# big-auv-power.net
KiCad netlist of a schematic drawn in Altium Designer
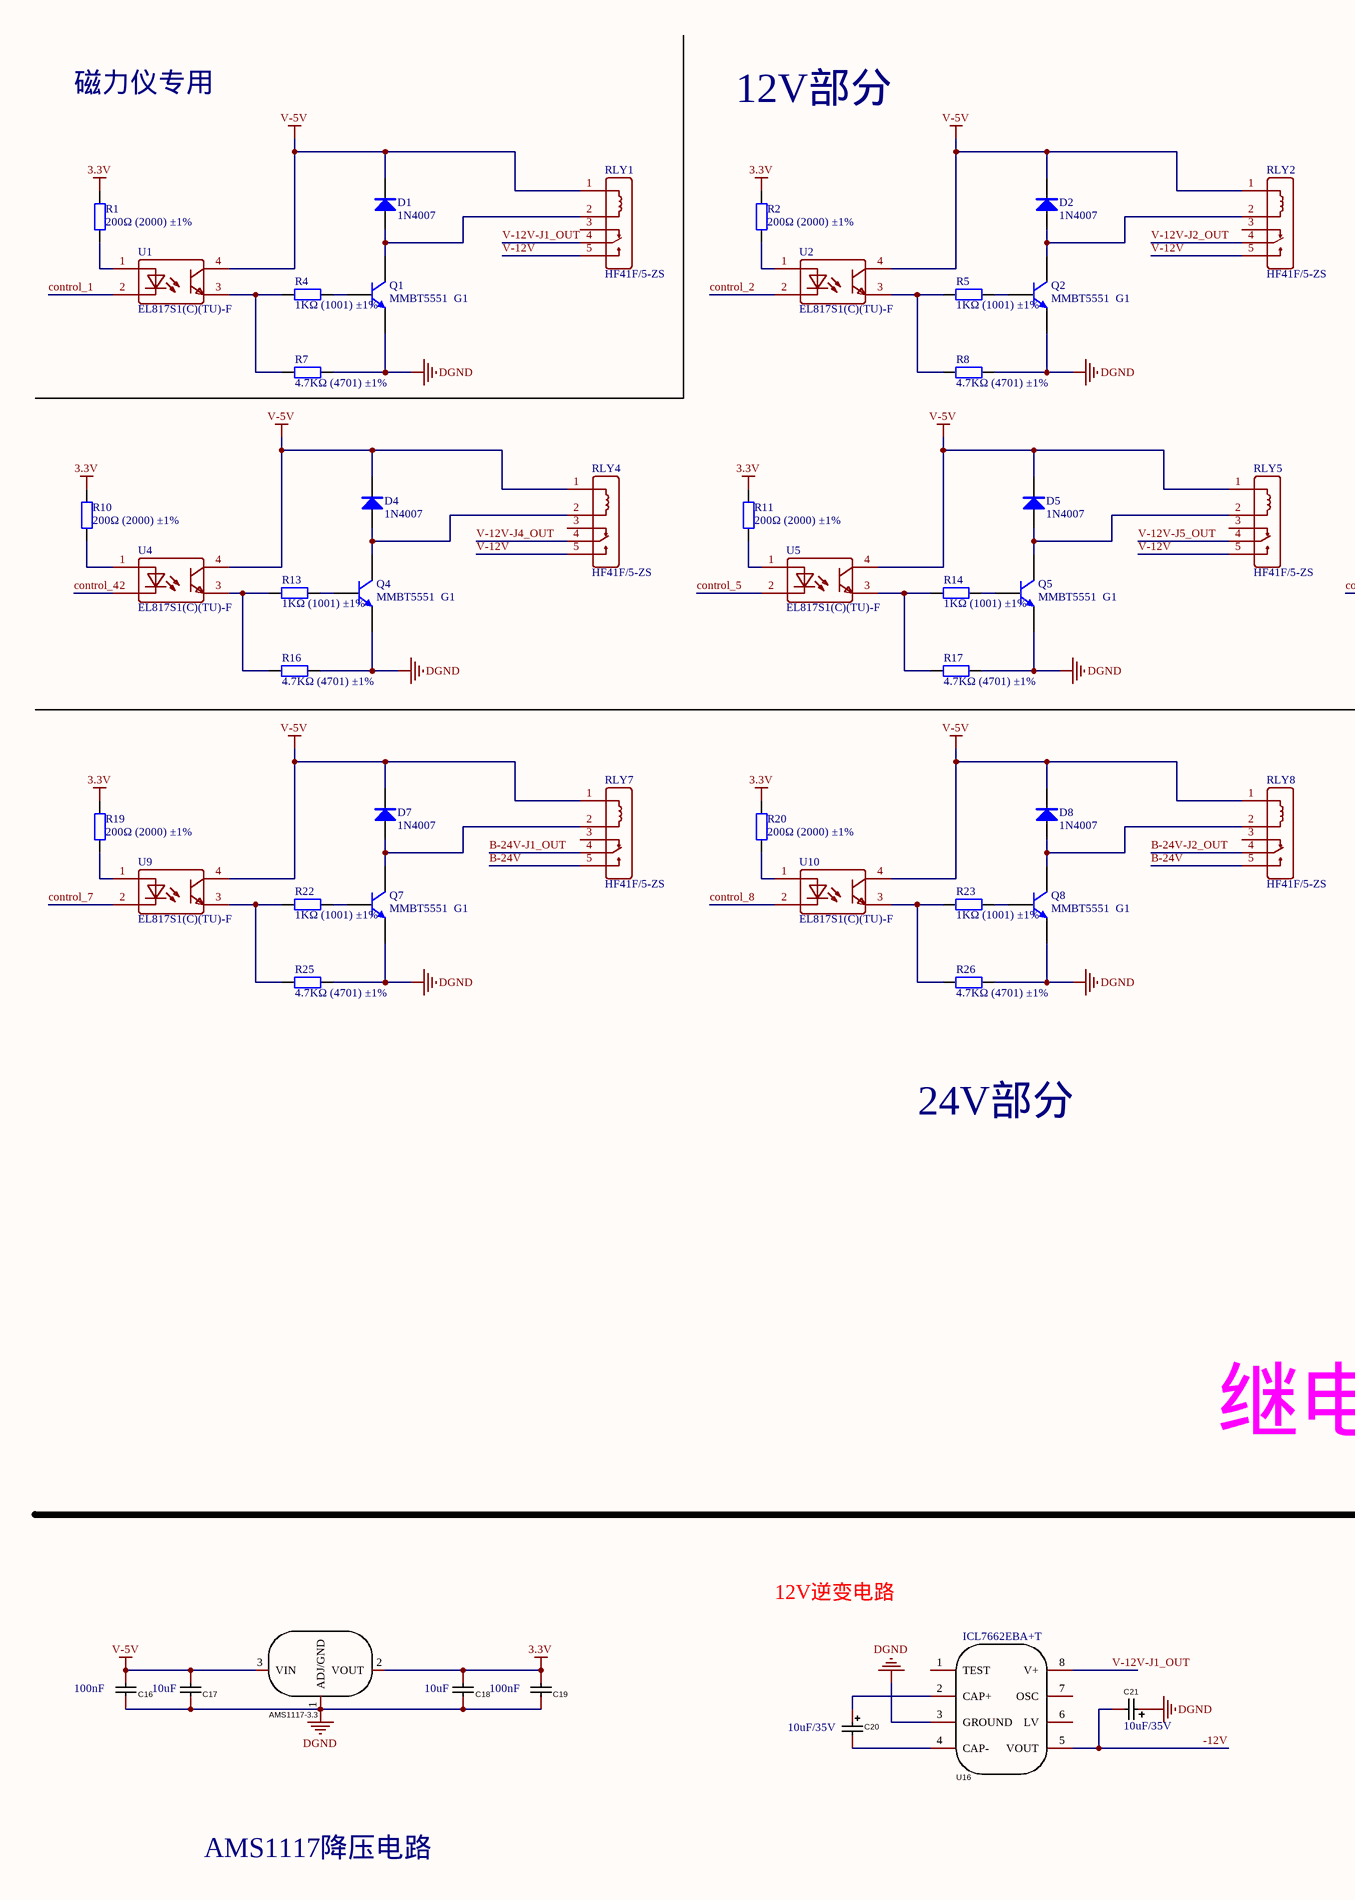
[diagram p0: big-auv-power.SchDoc, left]
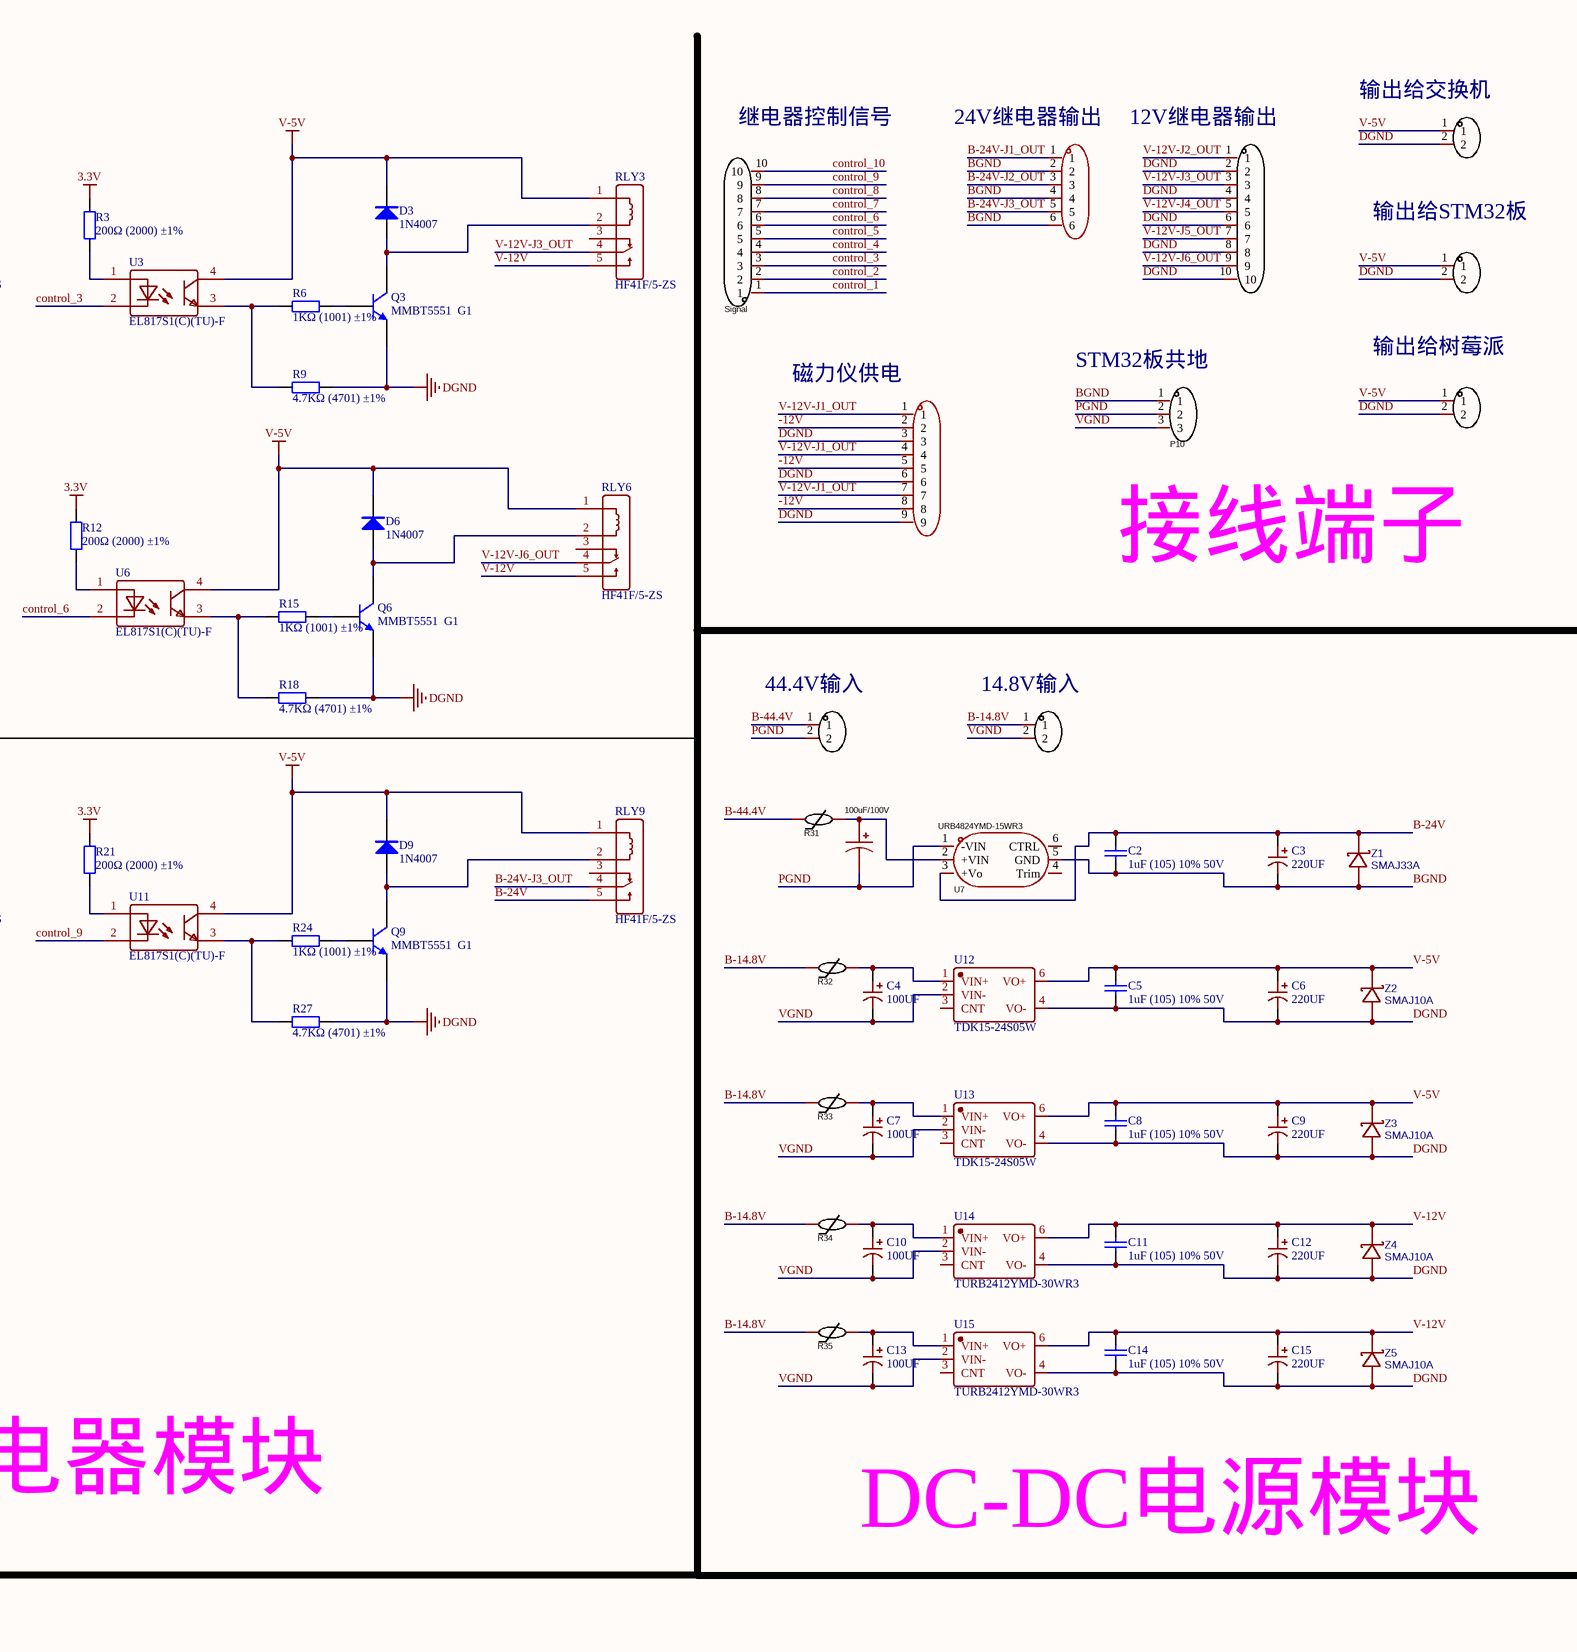
[diagram p1: big-auv-power.SchDoc, right]

(export (version "E")
  (design (tool "Eeschema 10.0.6"))
  (components
    (comp (ref "12V")
      (value "KF2EDGR-3.5-10P")
      (footprint "CONN-TH_10P-P3.50_KF2EDGR-3.5-10P")
      (fields (field (name "MANUFACTURER") "KEFA(科发)"))
      (libsource (lib "LC_Components") (part "KF2EDGR-3.5-10P"))
    )
    (comp (ref "24V")
      (value "KF2EDGR-3.5-6P")
      (footprint "CONN-TH_6P-P3.50_KF2EDGR-3.5-6P")
      (fields (field (name "MANUFACTURER") "KEFA(科发)"))
      (libsource (lib "LC_Components") (part "KF2EDGR-3.5-6P"))
    )
    (comp (ref "AMS1117-3.3")
      (value "A1117-3.3")
      (footprint "SOT-223-3_L6.5-W3.4-P2.30-LS7.0-BR-1")
      (fields (field (name "MANUFACTURER") "IDCHIP(英锐芯)"))
      (libsource (lib "LC_Components") (part "AMS1117-3.3"))
    )
    (comp (ref "C1")
      (value "100uF/100V")
      (footprint "CAP-SMD_BD12.5-L13.0-W13.0-FD-LS13.8")
      (description "100uF 100V电解电容")
      (fields (field (name "MANUFACTURER") "ROQANG(容强)") (field (name "MANUFACTURER PART") "RVT2A101M1213"))
      (libsource (lib "LC_Components") (part "RVT2A101M1213"))
    )
    (comp (ref "C2")
      (value "1uF (105) 10% 50V")
      (footprint "C0603")
      (description "贴片电容")
      (libsource (lib "2-Cap") (part "0603 1uF (105) 10% 50V"))
    )
    (comp (ref "C3") (value "220UF") (footprint "SMD-C") (libsource (lib "big-auv-power") (part "220UF")))
    (comp (ref "C4") (value "100UF") (footprint "SMD-C") (libsource (lib "big-auv-power") (part "100UF")))
    (comp (ref "C5")
      (value "1uF (105) 10% 50V")
      (footprint "C0603")
      (description "贴片电容")
      (libsource (lib "2-Cap") (part "0603 1uF (105) 10% 50V"))
    )
    (comp (ref "C6") (value "220UF") (footprint "SMD-C") (libsource (lib "big-auv-power") (part "220UF")))
    (comp (ref "C7") (value "100UF") (footprint "SMD-C") (libsource (lib "big-auv-power") (part "100UF")))
    (comp (ref "C8")
      (value "1uF (105) 10% 50V")
      (footprint "C0603")
      (description "贴片电容")
      (libsource (lib "2-Cap") (part "0603 1uF (105) 10% 50V"))
    )
    (comp (ref "C9") (value "220UF") (footprint "SMD-C") (libsource (lib "big-auv-power") (part "220UF")))
    (comp (ref "C10") (value "100UF") (footprint "SMD-C") (libsource (lib "big-auv-power") (part "100UF")))
    (comp (ref "C11")
      (value "1uF (105) 10% 50V")
      (footprint "C0603")
      (description "贴片电容")
      (libsource (lib "2-Cap") (part "0603 1uF (105) 10% 50V"))
    )
    (comp (ref "C12") (value "220UF") (footprint "SMD-C") (libsource (lib "big-auv-power") (part "220UF")))
    (comp (ref "C13") (value "100UF") (footprint "SMD-C") (libsource (lib "big-auv-power") (part "100UF")))
    (comp (ref "C14")
      (value "1uF (105) 10% 50V")
      (footprint "C0603")
      (description "贴片电容")
      (libsource (lib "2-Cap") (part "0603 1uF (105) 10% 50V"))
    )
    (comp (ref "C15") (value "220UF") (footprint "SMD-C") (libsource (lib "big-auv-power") (part "220UF")))
    (comp (ref "C16")
      (value "100nF")
      (footprint "C0603")
      (description "0603电容")
      (fields (field (name "MANUFACTURER") "FH(风华)") (field (name "MANUFACTURER PART") "0603B104K500NT"))
      (libsource (lib "LC_Components") (part "0603B104K500NT"))
    )
    (comp (ref "C17")
      (value "10uF")
      (footprint "C0603")
      (description "0603电容")
      (fields (field (name "MANUFACTURER") "FH(风华)") (field (name "MANUFACTURER PART") "0603B104K500NT"))
      (libsource (lib "LC_Components") (part "0603B104K500NT"))
    )
    (comp (ref "C18")
      (value "10uF")
      (footprint "C0603")
      (description "0603电容")
      (fields (field (name "MANUFACTURER") "FH(风华)") (field (name "MANUFACTURER PART") "0603B104K500NT"))
      (libsource (lib "LC_Components") (part "0603B104K500NT"))
    )
    (comp (ref "C19")
      (value "100nF")
      (footprint "C0603")
      (description "0603电容")
      (fields (field (name "MANUFACTURER") "FH(风华)") (field (name "MANUFACTURER PART") "0603B104K500NT"))
      (libsource (lib "LC_Components") (part "0603B104K500NT"))
    )
    (comp (ref "C20")
      (value "10uF/35V")
      (footprint "CASE-C_6032")
      (description "10uF/35V钽电容")
      (fields (field (name "MANUFACTURER") "Kyocera AVX") (field (name "MANUFACTURER PART") "TAJC106K035RNJ"))
      (libsource (lib "LC_Components") (part "TAJC106K035RNJ"))
    )
    (comp (ref "C21")
      (value "10uF/35V")
      (footprint "CASE-C_6032")
      (description "10uF/35V钽电容")
      (fields (field (name "MANUFACTURER") "Kyocera AVX") (field (name "MANUFACTURER PART") "TAJC106K035RNJ"))
      (libsource (lib "LC_Components") (part "TAJC106K035RNJ"))
    )
    (comp (ref "CILIYI")
      (value "KF2EDGR-3.5-9P")
      (footprint "CONN-TH_9P-P3.50_KF2EDGR-3.5-9P")
      (fields (field (name "MANUFACTURER") "KEFA(科发)"))
      (libsource (lib "LC_Components") (part "KF2EDGR-3.5-9P"))
    )
    (comp (ref "D1")
      (value "1N4007")
      (footprint "SMA(DO-214AC)_S2")
      (description "整流二极管")
      (fields (field (name "版权归属") "源创客"))
      (libsource (lib "4-Diode") (part "1N4007"))
    )
    (comp (ref "D2")
      (value "1N4007")
      (footprint "SMA(DO-214AC)_S2")
      (description "整流二极管")
      (fields (field (name "版权归属") "源创客"))
      (libsource (lib "4-Diode") (part "1N4007"))
    )
    (comp (ref "D3")
      (value "1N4007")
      (footprint "SMA(DO-214AC)_S2")
      (description "整流二极管")
      (fields (field (name "版权归属") "源创客"))
      (libsource (lib "4-Diode") (part "1N4007"))
    )
    (comp (ref "D4")
      (value "1N4007")
      (footprint "SMA(DO-214AC)_S2")
      (description "整流二极管")
      (fields (field (name "版权归属") "源创客"))
      (libsource (lib "4-Diode") (part "1N4007"))
    )
    (comp (ref "D5")
      (value "1N4007")
      (footprint "SMA(DO-214AC)_S2")
      (description "整流二极管")
      (fields (field (name "版权归属") "源创客"))
      (libsource (lib "4-Diode") (part "1N4007"))
    )
    (comp (ref "D6")
      (value "1N4007")
      (footprint "SMA(DO-214AC)_S2")
      (description "整流二极管")
      (fields (field (name "版权归属") "源创客"))
      (libsource (lib "4-Diode") (part "1N4007"))
    )
    (comp (ref "D7")
      (value "1N4007")
      (footprint "SMA(DO-214AC)_S2")
      (description "整流二极管")
      (fields (field (name "版权归属") "源创客"))
      (libsource (lib "4-Diode") (part "1N4007"))
    )
    (comp (ref "D8")
      (value "1N4007")
      (footprint "SMA(DO-214AC)_S2")
      (description "整流二极管")
      (fields (field (name "版权归属") "源创客"))
      (libsource (lib "4-Diode") (part "1N4007"))
    )
    (comp (ref "D9")
      (value "1N4007")
      (footprint "SMA(DO-214AC)_S2")
      (description "整流二极管")
      (fields (field (name "版权归属") "源创客"))
      (libsource (lib "4-Diode") (part "1N4007"))
    )
    (comp (ref "JP1")
      (value "KF2EDGR-3.81-2P")
      (footprint "CONN-TH_2P-P3.81_KF2EDGR-3.81-2P")
      (fields (field (name "MANUFACTURER") "KEFA(科发)"))
      (libsource (lib "LC_Components") (part "KF2EDGR-3.81-2P"))
    )
    (comp (ref "JP2")
      (value "KF2EDGR-3.81-2P")
      (footprint "CONN-TH_2P-P3.81_KF2EDGR-3.81-2P")
      (fields (field (name "MANUFACTURER") "KEFA(科发)"))
      (libsource (lib "LC_Components") (part "KF2EDGR-3.81-2P"))
    )
    (comp (ref "JP3")
      (value "KF2EDGR-3.81-2P")
      (footprint "CONN-TH_2P-P3.81_KF2EDGR-3.81-2P")
      (fields (field (name "MANUFACTURER") "KEFA(科发)"))
      (libsource (lib "LC_Components") (part "KF2EDGR-3.81-2P"))
    )
    (comp (ref "P6")
      (value "KF2EDGV-5.08-2P")
      (footprint "CONN-TH_P5.08_KF2EDGV-5.08-2P")
      (fields (field (name "MANUFACTURER") "KEFA(科发)"))
      (libsource (lib "LC_Components") (part "KF2EDGV-5.08-2P"))
    )
    (comp (ref "P7")
      (value "KF2EDGV-5.08-2P")
      (footprint "CONN-TH_P5.08_KF2EDGV-5.08-2P")
      (fields (field (name "MANUFACTURER") "KEFA(科发)"))
      (libsource (lib "LC_Components") (part "KF2EDGV-5.08-2P"))
    )
    (comp (ref "P10")
      (value "KF2EDGR-3.81-3P")
      (footprint "CONN-TH_3P-P3.81_KF2EDGR-3.81-3P")
      (fields (field (name "MANUFACTURER") "KEFA(科发)"))
      (libsource (lib "LC_Components") (part "KF2EDGR-3.81-3P"))
    )
    (comp (ref "Q1")
      (value "MMBT5551  G1")
      (footprint "SOT-23-3_L2.9-W1.3-P1.90-LS2.4-BR")
      (description "三极管")
      (libsource (lib "7-Transistor_NPN") (part "SOT-23 MMBT5551  G1"))
    )
    (comp (ref "Q2")
      (value "MMBT5551  G1")
      (footprint "SOT-23-3_L2.9-W1.3-P1.90-LS2.4-BR")
      (description "三极管")
      (libsource (lib "7-Transistor_NPN") (part "SOT-23 MMBT5551  G1"))
    )
    (comp (ref "Q3")
      (value "MMBT5551  G1")
      (footprint "SOT-23-3_L2.9-W1.3-P1.90-LS2.4-BR")
      (description "三极管")
      (libsource (lib "7-Transistor_NPN") (part "SOT-23 MMBT5551  G1"))
    )
    (comp (ref "Q4")
      (value "MMBT5551  G1")
      (footprint "SOT-23-3_L2.9-W1.3-P1.90-LS2.4-BR")
      (description "三极管")
      (libsource (lib "7-Transistor_NPN") (part "SOT-23 MMBT5551  G1"))
    )
    (comp (ref "Q5")
      (value "MMBT5551  G1")
      (footprint "SOT-23-3_L2.9-W1.3-P1.90-LS2.4-BR")
      (description "三极管")
      (libsource (lib "7-Transistor_NPN") (part "SOT-23 MMBT5551  G1"))
    )
    (comp (ref "Q6")
      (value "MMBT5551  G1")
      (footprint "SOT-23-3_L2.9-W1.3-P1.90-LS2.4-BR")
      (description "三极管")
      (libsource (lib "7-Transistor_NPN") (part "SOT-23 MMBT5551  G1"))
    )
    (comp (ref "Q7")
      (value "MMBT5551  G1")
      (footprint "SOT-23-3_L2.9-W1.3-P1.90-LS2.4-BR")
      (description "三极管")
      (libsource (lib "7-Transistor_NPN") (part "SOT-23 MMBT5551  G1"))
    )
    (comp (ref "Q8")
      (value "MMBT5551  G1")
      (footprint "SOT-23-3_L2.9-W1.3-P1.90-LS2.4-BR")
      (description "三极管")
      (libsource (lib "7-Transistor_NPN") (part "SOT-23 MMBT5551  G1"))
    )
    (comp (ref "Q9")
      (value "MMBT5551  G1")
      (footprint "SOT-23-3_L2.9-W1.3-P1.90-LS2.4-BR")
      (description "三极管")
      (libsource (lib "7-Transistor_NPN") (part "SOT-23 MMBT5551  G1"))
    )
    (comp (ref "R1")
      (value "200Ω (2000) ±1%")
      (footprint "R0603")
      (description "贴片电阻")
      (libsource (lib "1-RES") (part "0603 200Ω (2000) 1%"))
    )
    (comp (ref "R2")
      (value "200Ω (2000) ±1%")
      (footprint "R0603")
      (description "贴片电阻")
      (libsource (lib "1-RES") (part "0603 200Ω (2000) 1%"))
    )
    (comp (ref "R3")
      (value "200Ω (2000) ±1%")
      (footprint "R0603")
      (description "贴片电阻")
      (libsource (lib "1-RES") (part "0603 200Ω (2000) 1%"))
    )
    (comp (ref "R4")
      (value "1KΩ (1001) ±1%")
      (footprint "R0603")
      (description "贴片电阻")
      (libsource (lib "1-RES") (part "0603 1KΩ (1001) 1%"))
    )
    (comp (ref "R5")
      (value "1KΩ (1001) ±1%")
      (footprint "R0603")
      (description "贴片电阻")
      (libsource (lib "1-RES") (part "0603 1KΩ (1001) 1%"))
    )
    (comp (ref "R6")
      (value "1KΩ (1001) ±1%")
      (footprint "R0603")
      (description "贴片电阻")
      (libsource (lib "1-RES") (part "0603 1KΩ (1001) 1%"))
    )
    (comp (ref "R7")
      (value "4.7KΩ (4701) ±1%")
      (footprint "R0603")
      (description "贴片电阻")
      (libsource (lib "1-RES") (part "0603 4.7KΩ (4701) 1%"))
    )
    (comp (ref "R8")
      (value "4.7KΩ (4701) ±1%")
      (footprint "R0603")
      (description "贴片电阻")
      (libsource (lib "1-RES") (part "0603 4.7KΩ (4701) 1%"))
    )
    (comp (ref "R9")
      (value "4.7KΩ (4701) ±1%")
      (footprint "R0603")
      (description "贴片电阻")
      (libsource (lib "1-RES") (part "0603 4.7KΩ (4701) 1%"))
    )
    (comp (ref "R10")
      (value "200Ω (2000) ±1%")
      (footprint "R0603")
      (description "贴片电阻")
      (libsource (lib "1-RES") (part "0603 200Ω (2000) 1%"))
    )
    (comp (ref "R11")
      (value "200Ω (2000) ±1%")
      (footprint "R0603")
      (description "贴片电阻")
      (libsource (lib "1-RES") (part "0603 200Ω (2000) 1%"))
    )
    (comp (ref "R12")
      (value "200Ω (2000) ±1%")
      (footprint "R0603")
      (description "贴片电阻")
      (libsource (lib "1-RES") (part "0603 200Ω (2000) 1%"))
    )
    (comp (ref "R13")
      (value "1KΩ (1001) ±1%")
      (footprint "R0603")
      (description "贴片电阻")
      (libsource (lib "1-RES") (part "0603 1KΩ (1001) 1%"))
    )
    (comp (ref "R14")
      (value "1KΩ (1001) ±1%")
      (footprint "R0603")
      (description "贴片电阻")
      (libsource (lib "1-RES") (part "0603 1KΩ (1001) 1%"))
    )
    (comp (ref "R15")
      (value "1KΩ (1001) ±1%")
      (footprint "R0603")
      (description "贴片电阻")
      (libsource (lib "1-RES") (part "0603 1KΩ (1001) 1%"))
    )
    (comp (ref "R16")
      (value "4.7KΩ (4701) ±1%")
      (footprint "R0603")
      (description "贴片电阻")
      (libsource (lib "1-RES") (part "0603 4.7KΩ (4701) 1%"))
    )
    (comp (ref "R17")
      (value "4.7KΩ (4701) ±1%")
      (footprint "R0603")
      (description "贴片电阻")
      (libsource (lib "1-RES") (part "0603 4.7KΩ (4701) 1%"))
    )
    (comp (ref "R18")
      (value "4.7KΩ (4701) ±1%")
      (footprint "R0603")
      (description "贴片电阻")
      (libsource (lib "1-RES") (part "0603 4.7KΩ (4701) 1%"))
    )
    (comp (ref "R19")
      (value "200Ω (2000) ±1%")
      (footprint "R0603")
      (description "贴片电阻")
      (libsource (lib "1-RES") (part "0603 200Ω (2000) 1%"))
    )
    (comp (ref "R20")
      (value "200Ω (2000) ±1%")
      (footprint "R0603")
      (description "贴片电阻")
      (libsource (lib "1-RES") (part "0603 200Ω (2000) 1%"))
    )
    (comp (ref "R21")
      (value "200Ω (2000) ±1%")
      (footprint "R0603")
      (description "贴片电阻")
      (libsource (lib "1-RES") (part "0603 200Ω (2000) 1%"))
    )
    (comp (ref "R22")
      (value "1KΩ (1001) ±1%")
      (footprint "R0603")
      (description "贴片电阻")
      (libsource (lib "1-RES") (part "0603 1KΩ (1001) 1%"))
    )
    (comp (ref "R23")
      (value "1KΩ (1001) ±1%")
      (footprint "R0603")
      (description "贴片电阻")
      (libsource (lib "1-RES") (part "0603 1KΩ (1001) 1%"))
    )
    (comp (ref "R24")
      (value "1KΩ (1001) ±1%")
      (footprint "R0603")
      (description "贴片电阻")
      (libsource (lib "1-RES") (part "0603 1KΩ (1001) 1%"))
    )
    (comp (ref "R25")
      (value "4.7KΩ (4701) ±1%")
      (footprint "R0603")
      (description "贴片电阻")
      (libsource (lib "1-RES") (part "0603 4.7KΩ (4701) 1%"))
    )
    (comp (ref "R26")
      (value "4.7KΩ (4701) ±1%")
      (footprint "R0603")
      (description "贴片电阻")
      (libsource (lib "1-RES") (part "0603 4.7KΩ (4701) 1%"))
    )
    (comp (ref "R27")
      (value "4.7KΩ (4701) ±1%")
      (footprint "R0603")
      (description "贴片电阻")
      (libsource (lib "1-RES") (part "0603 4.7KΩ (4701) 1%"))
    )
    (comp (ref "R31")
      (value "MF72 22D9")
      (footprint "RES-TH_L12.5-W5.1-P7.50-D1.2-S2.20")
      (description "NTC热敏电阻")
      (fields (field (name "MANUFACTURER") "时恒") (field (name "POWER") "2W"))
      (libsource (lib "LC_Components") (part "MF72 22D9"))
    )
    (comp (ref "R32")
      (value "MF72 22D9")
      (footprint "RES-TH_L12.5-W5.1-P7.50-D1.2-S2.20")
      (description "NTC热敏电阻")
      (fields (field (name "MANUFACTURER") "时恒") (field (name "POWER") "2W"))
      (libsource (lib "LC_Components") (part "MF72 22D9"))
    )
    (comp (ref "R33")
      (value "MF72 22D9")
      (footprint "RES-TH_L12.5-W5.1-P7.50-D1.2-S2.20")
      (description "NTC热敏电阻")
      (fields (field (name "MANUFACTURER") "时恒") (field (name "POWER") "2W"))
      (libsource (lib "LC_Components") (part "MF72 22D9"))
    )
    (comp (ref "R34")
      (value "MF72 22D9")
      (footprint "RES-TH_L12.5-W5.1-P7.50-D1.2-S2.20")
      (description "NTC热敏电阻")
      (fields (field (name "MANUFACTURER") "时恒") (field (name "POWER") "2W"))
      (libsource (lib "LC_Components") (part "MF72 22D9"))
    )
    (comp (ref "R35")
      (value "MF72 22D9")
      (footprint "RES-TH_L12.5-W5.1-P7.50-D1.2-S2.20")
      (description "NTC热敏电阻")
      (fields (field (name "MANUFACTURER") "时恒") (field (name "POWER") "2W"))
      (libsource (lib "LC_Components") (part "MF72 22D9"))
    )
    (comp (ref "RLY1")
      (value "HF41F/5-ZS")
      (footprint "HF41F/5-ZS")
      (libsource (lib "big-auv-power") (part "HF41F/5-ZS"))
    )
    (comp (ref "RLY2")
      (value "HF41F/5-ZS")
      (footprint "HF41F/5-ZS")
      (libsource (lib "big-auv-power") (part "HF41F/5-ZS"))
    )
    (comp (ref "RLY3")
      (value "HF41F/5-ZS")
      (footprint "HF41F/5-ZS")
      (libsource (lib "big-auv-power") (part "HF41F/5-ZS"))
    )
    (comp (ref "RLY4")
      (value "HF41F/5-ZS")
      (footprint "HF41F/5-ZS")
      (libsource (lib "big-auv-power") (part "HF41F/5-ZS"))
    )
    (comp (ref "RLY5")
      (value "HF41F/5-ZS")
      (footprint "HF41F/5-ZS")
      (libsource (lib "big-auv-power") (part "HF41F/5-ZS"))
    )
    (comp (ref "RLY6")
      (value "HF41F/5-ZS")
      (footprint "HF41F/5-ZS")
      (libsource (lib "big-auv-power") (part "HF41F/5-ZS"))
    )
    (comp (ref "RLY7")
      (value "HF41F/5-ZS")
      (footprint "HF41F/5-ZS")
      (libsource (lib "big-auv-power") (part "HF41F/5-ZS"))
    )
    (comp (ref "RLY8")
      (value "HF41F/5-ZS")
      (footprint "HF41F/5-ZS")
      (libsource (lib "big-auv-power") (part "HF41F/5-ZS"))
    )
    (comp (ref "RLY9")
      (value "HF41F/5-ZS")
      (footprint "HF41F/5-ZS")
      (libsource (lib "big-auv-power") (part "HF41F/5-ZS"))
    )
    (comp (ref "Signal")
      (value "KF2EDGR-3.5-10P")
      (footprint "CONN-TH_10P-P3.50_KF2EDGR-3.5-10P")
      (fields (field (name "MANUFACTURER") "KEFA(科发)"))
      (libsource (lib "LC_Components") (part "KF2EDGR-3.5-10P"))
    )
    (comp (ref "U1")
      (value "EL817S1(C)(TU)-F")
      (footprint "EL817S1(C)(TU)-F")
      (libsource (lib "big-auv-power") (part "EL817S1(C)(TU)-F"))
    )
    (comp (ref "U2")
      (value "EL817S1(C)(TU)-F")
      (footprint "EL817S1(C)(TU)-F")
      (libsource (lib "big-auv-power") (part "EL817S1(C)(TU)-F"))
    )
    (comp (ref "U3")
      (value "EL817S1(C)(TU)-F")
      (footprint "EL817S1(C)(TU)-F")
      (libsource (lib "big-auv-power") (part "EL817S1(C)(TU)-F"))
    )
    (comp (ref "U4")
      (value "EL817S1(C)(TU)-F")
      (footprint "EL817S1(C)(TU)-F")
      (libsource (lib "big-auv-power") (part "EL817S1(C)(TU)-F"))
    )
    (comp (ref "U5")
      (value "EL817S1(C)(TU)-F")
      (footprint "EL817S1(C)(TU)-F")
      (libsource (lib "big-auv-power") (part "EL817S1(C)(TU)-F"))
    )
    (comp (ref "U6")
      (value "EL817S1(C)(TU)-F")
      (footprint "EL817S1(C)(TU)-F")
      (libsource (lib "big-auv-power") (part "EL817S1(C)(TU)-F"))
    )
    (comp (ref "U7")
      (value "URB4824YMD-15WR3")
      (footprint "PWRM-TH_YLPTEC_URBXXXXYMD-15WR3")
      (description "48V转24V降压模块")
      (fields (field (name "MANUFACTURER") "YLPTEC(易川)") (field (name "POWER") "15W"))
      (libsource (lib "LC_Components") (part "URB4824YMD-15WR3_C5369771"))
    )
    (comp (ref "U9")
      (value "EL817S1(C)(TU)-F")
      (footprint "EL817S1(C)(TU)-F")
      (libsource (lib "big-auv-power") (part "EL817S1(C)(TU)-F"))
    )
    (comp (ref "U10")
      (value "EL817S1(C)(TU)-F")
      (footprint "EL817S1(C)(TU)-F")
      (libsource (lib "big-auv-power") (part "EL817S1(C)(TU)-F"))
    )
    (comp (ref "U11")
      (value "EL817S1(C)(TU)-F")
      (footprint "EL817S1(C)(TU)-F")
      (libsource (lib "big-auv-power") (part "EL817S1(C)(TU)-F"))
    )
    (comp (ref "U12")
      (value "TDK15-24S05W")
      (footprint "TDK15-24S05")
      (libsource (lib "big-auv-power") (part "TDK15-24S05"))
    )
    (comp (ref "U13")
      (value "TDK15-24S05W")
      (footprint "TDK15-24S05")
      (libsource (lib "big-auv-power") (part "TDK15-24S05"))
    )
    (comp (ref "U14")
      (value "TURB2412YMD-30WR3")
      (footprint "TDK15-24S05")
      (libsource (lib "big-auv-power") (part "TDK15-24S05"))
    )
    (comp (ref "U15")
      (value "TURB2412YMD-30WR3")
      (footprint "TDK15-24S05")
      (libsource (lib "big-auv-power") (part "TDK15-24S05"))
    )
    (comp (ref "U16")
      (value "ICL7662EBA+T")
      (footprint "SOIC-8_L5.0-W4.0-P1.27-LS6.0-BL")
      (description "宽幅电压逆变")
      (fields (field (name "MANUFACTURER") "ADI(亚德诺)/MAXIM(美信)"))
      (libsource (lib "LC_Components") (part "ICL7662EBA+T"))
    )
    (comp (ref "Z1")
      (value "SMAJ33A")
      (footprint "SMA(DO-214AC)")
      (description "TVS二极管")
      (fields
        (field (name "BOM_SUPPLIER PART") "C151250")
        (field (name "BOM_MANUFACTURER PART") "SMBJ10A")
        (field (name "CONTRIBUTOR") "LCSC")
      )
      (libsource (lib "4-Diode") (part "SMBJ10A"))
    )
    (comp (ref "Z2")
      (value "SMAJ10A")
      (footprint "SMA(DO-214AC)")
      (description "TVS二极管")
      (fields
        (field (name "BOM_SUPPLIER PART") "C151250")
        (field (name "BOM_MANUFACTURER PART") "SMBJ10A")
        (field (name "CONTRIBUTOR") "LCSC")
      )
      (libsource (lib "4-Diode") (part "SMBJ10A"))
    )
    (comp (ref "Z3")
      (value "SMAJ10A")
      (footprint "SMA(DO-214AC)")
      (description "TVS二极管")
      (fields
        (field (name "BOM_SUPPLIER PART") "C151250")
        (field (name "BOM_MANUFACTURER PART") "SMBJ10A")
        (field (name "CONTRIBUTOR") "LCSC")
      )
      (libsource (lib "4-Diode") (part "SMBJ10A"))
    )
    (comp (ref "Z4")
      (value "SMAJ10A")
      (footprint "SMA(DO-214AC)")
      (description "TVS二极管")
      (fields
        (field (name "BOM_SUPPLIER PART") "C151250")
        (field (name "BOM_MANUFACTURER PART") "SMBJ10A")
        (field (name "CONTRIBUTOR") "LCSC")
      )
      (libsource (lib "4-Diode") (part "SMBJ10A"))
    )
    (comp (ref "Z5")
      (value "SMAJ10A")
      (footprint "SMA(DO-214AC)")
      (description "TVS二极管")
      (fields
        (field (name "BOM_SUPPLIER PART") "C151250")
        (field (name "BOM_MANUFACTURER PART") "SMBJ10A")
        (field (name "CONTRIBUTOR") "LCSC")
      )
      (libsource (lib "4-Diode") (part "SMBJ10A"))
    )
  )
  (nets
    (net (code "1") (name "/-12V") (class "Default")
      (node (ref "C21") (pin "2") (pinfunction "2_2") (pintype "passive"))
      (node (ref "CILIYI") (pin "2") (pinfunction "2_2") (pintype "passive"))
      (node (ref "CILIYI") (pin "5") (pinfunction "5_5") (pintype "passive"))
      (node (ref "CILIYI") (pin "8") (pinfunction "8_8") (pintype "passive"))
      (node (ref "U16") (pin "5") (pinfunction "VOUT_5") (pintype "passive"))
    )
    (net (code "2") (name "/B-14.8V") (class "Default")
      (node (ref "P7") (pin "1") (pinfunction "1_1") (pintype "passive"))
      (node (ref "R32") (pin "1") (pinfunction "1_1") (pintype "passive"))
      (node (ref "R33") (pin "1") (pinfunction "1_1") (pintype "passive"))
      (node (ref "R34") (pin "1") (pinfunction "1_1") (pintype "passive"))
      (node (ref "R35") (pin "1") (pinfunction "1_1") (pintype "passive"))
    )
    (net (code "3") (name "/B-24V") (class "Default")
      (node (ref "C2") (pin "1") (pinfunction "1_1") (pintype "passive"))
      (node (ref "C3") (pin "1") (pinfunction "1_1") (pintype "passive"))
      (node (ref "RLY7") (pin "5") (pinfunction "NO_5") (pintype "passive"))
      (node (ref "RLY8") (pin "5") (pinfunction "NO_5") (pintype "passive"))
      (node (ref "RLY9") (pin "5") (pinfunction "NO_5") (pintype "passive"))
      (node (ref "U7") (pin "3") (pinfunction "+Vo_3") (pintype "passive"))
      (node (ref "Z1") (pin "2") (pinfunction "K_2") (pintype "passive"))
    )
    (net (code "4") (name "/B-24V-J1_OUT") (class "Default")
      (node (ref "24V") (pin "1") (pinfunction "1_1") (pintype "passive"))
      (node (ref "RLY7") (pin "4") (pinfunction "COM_4") (pintype "passive"))
    )
    (net (code "5") (name "/B-24V-J2_OUT") (class "Default")
      (node (ref "24V") (pin "3") (pinfunction "3_3") (pintype "passive"))
      (node (ref "RLY8") (pin "4") (pinfunction "COM_4") (pintype "passive"))
    )
    (net (code "6") (name "/B-24V-J3_OUT") (class "Default")
      (node (ref "24V") (pin "5") (pinfunction "5_5") (pintype "passive"))
      (node (ref "RLY9") (pin "4") (pinfunction "COM_4") (pintype "passive"))
    )
    (net (code "7") (name "/B-44.4V") (class "Default")
      (node (ref "P6") (pin "1") (pinfunction "1_1") (pintype "passive"))
      (node (ref "R31") (pin "1") (pinfunction "1_1") (pintype "passive"))
    )
    (net (code "8") (name "/BGND") (class "Default")
      (node (ref "24V") (pin "2") (pinfunction "2_2") (pintype "passive"))
      (node (ref "24V") (pin "4") (pinfunction "4_4") (pintype "passive"))
      (node (ref "24V") (pin "6") (pinfunction "6_6") (pintype "passive"))
      (node (ref "C2") (pin "2") (pinfunction "2_2") (pintype "passive"))
      (node (ref "C3") (pin "2") (pinfunction "2_2") (pintype "passive"))
      (node (ref "P10") (pin "1") (pinfunction "1_1") (pintype "passive"))
      (node (ref "U7") (pin "5") (pinfunction "GND_5") (pintype "passive"))
      (node (ref "Z1") (pin "1") (pinfunction "A_1") (pintype "passive"))
    )
    (net (code "9") (name "/PGND") (class "Default")
      (node (ref "C1") (pin "2") (pinfunction "2_2") (pintype "passive"))
      (node (ref "P10") (pin "2") (pinfunction "2_2") (pintype "passive"))
      (node (ref "P6") (pin "2") (pinfunction "2_2") (pintype "passive"))
      (node (ref "U7") (pin "1") (pinfunction "-VIN_1") (pintype "passive"))
    )
    (net (code "10") (name "/V-12V") (class "Default")
      (node (ref "C11") (pin "1") (pinfunction "1_1") (pintype "passive"))
      (node (ref "C12") (pin "1") (pinfunction "1_1") (pintype "passive"))
      (node (ref "C14") (pin "1") (pinfunction "1_1") (pintype "passive"))
      (node (ref "C15") (pin "1") (pinfunction "1_1") (pintype "passive"))
      (node (ref "RLY1") (pin "5") (pinfunction "NO_5") (pintype "passive"))
      (node (ref "RLY2") (pin "5") (pinfunction "NO_5") (pintype "passive"))
      (node (ref "RLY3") (pin "5") (pinfunction "NO_5") (pintype "passive"))
      (node (ref "RLY4") (pin "5") (pinfunction "NO_5") (pintype "passive"))
      (node (ref "RLY5") (pin "5") (pinfunction "NO_5") (pintype "passive"))
      (node (ref "RLY6") (pin "5") (pinfunction "NO_5") (pintype "passive"))
      (node (ref "U14") (pin "6") (pinfunction "VO+_6") (pintype "passive"))
      (node (ref "U15") (pin "6") (pinfunction "VO+_6") (pintype "passive"))
      (node (ref "Z4") (pin "2") (pinfunction "K_2") (pintype "passive"))
      (node (ref "Z5") (pin "2") (pinfunction "K_2") (pintype "passive"))
    )
    (net (code "11") (name "/V-12V-J1_OUT") (class "Default")
      (node (ref "CILIYI") (pin "1") (pinfunction "1_1") (pintype "passive"))
      (node (ref "CILIYI") (pin "4") (pinfunction "4_4") (pintype "passive"))
      (node (ref "CILIYI") (pin "7") (pinfunction "7_7") (pintype "passive"))
      (node (ref "RLY1") (pin "4") (pinfunction "COM_4") (pintype "passive"))
      (node (ref "U16") (pin "8") (pinfunction "V+_8") (pintype "passive"))
    )
    (net (code "12") (name "/V-12V-J2_OUT") (class "Default")
      (node (ref "12V") (pin "1") (pinfunction "1_1") (pintype "passive"))
      (node (ref "RLY2") (pin "4") (pinfunction "COM_4") (pintype "passive"))
    )
    (net (code "13") (name "/V-12V-J3_OUT") (class "Default")
      (node (ref "12V") (pin "3") (pinfunction "3_3") (pintype "passive"))
      (node (ref "RLY3") (pin "4") (pinfunction "COM_4") (pintype "passive"))
    )
    (net (code "14") (name "/V-12V-J4_OUT") (class "Default")
      (node (ref "12V") (pin "5") (pinfunction "5_5") (pintype "passive"))
      (node (ref "RLY4") (pin "4") (pinfunction "COM_4") (pintype "passive"))
    )
    (net (code "15") (name "/V-12V-J5_OUT") (class "Default")
      (node (ref "12V") (pin "7") (pinfunction "7_7") (pintype "passive"))
      (node (ref "RLY5") (pin "4") (pinfunction "COM_4") (pintype "passive"))
    )
    (net (code "16") (name "/V-12V-J6_OUT") (class "Default")
      (node (ref "12V") (pin "9") (pinfunction "9_9") (pintype "passive"))
      (node (ref "RLY6") (pin "4") (pinfunction "COM_4") (pintype "passive"))
    )
    (net (code "17") (name "/VGND") (class "Default")
      (node (ref "C10") (pin "2") (pinfunction "2_2") (pintype "passive"))
      (node (ref "C13") (pin "2") (pinfunction "2_2") (pintype "passive"))
      (node (ref "C4") (pin "2") (pinfunction "2_2") (pintype "passive"))
      (node (ref "C7") (pin "2") (pinfunction "2_2") (pintype "passive"))
      (node (ref "P10") (pin "3") (pinfunction "3_3") (pintype "passive"))
      (node (ref "P7") (pin "2") (pinfunction "2_2") (pintype "passive"))
      (node (ref "U12") (pin "2") (pinfunction "VIN-_2") (pintype "passive"))
      (node (ref "U13") (pin "2") (pinfunction "VIN-_2") (pintype "passive"))
      (node (ref "U14") (pin "2") (pinfunction "VIN-_2") (pintype "passive"))
      (node (ref "U15") (pin "2") (pinfunction "VIN-_2") (pintype "passive"))
    )
    (net (code "18") (name "/control_1") (class "Default")
      (node (ref "Signal") (pin "1") (pinfunction "1_1") (pintype "passive"))
      (node (ref "U1") (pin "2") (pinfunction "CAT_2") (pintype "passive"))
    )
    (net (code "19") (name "/control_2") (class "Default")
      (node (ref "Signal") (pin "2") (pinfunction "2_2") (pintype "passive"))
      (node (ref "U2") (pin "2") (pinfunction "CAT_2") (pintype "passive"))
    )
    (net (code "20") (name "/control_3") (class "Default")
      (node (ref "Signal") (pin "3") (pinfunction "3_3") (pintype "passive"))
      (node (ref "U3") (pin "2") (pinfunction "CAT_2") (pintype "passive"))
    )
    (net (code "21") (name "/control_4") (class "Default")
      (node (ref "Signal") (pin "4") (pinfunction "4_4") (pintype "passive"))
      (node (ref "U4") (pin "2") (pinfunction "CAT_2") (pintype "passive"))
    )
    (net (code "22") (name "/control_5") (class "Default")
      (node (ref "Signal") (pin "5") (pinfunction "5_5") (pintype "passive"))
      (node (ref "U5") (pin "2") (pinfunction "CAT_2") (pintype "passive"))
    )
    (net (code "23") (name "/control_6") (class "Default")
      (node (ref "Signal") (pin "6") (pinfunction "6_6") (pintype "passive"))
      (node (ref "U6") (pin "2") (pinfunction "CAT_2") (pintype "passive"))
    )
    (net (code "24") (name "/control_7") (class "Default")
      (node (ref "Signal") (pin "7") (pinfunction "7_7") (pintype "passive"))
      (node (ref "U9") (pin "2") (pinfunction "CAT_2") (pintype "passive"))
    )
    (net (code "25") (name "/control_8") (class "Default")
      (node (ref "Signal") (pin "8") (pinfunction "8_8") (pintype "passive"))
      (node (ref "U10") (pin "2") (pinfunction "CAT_2") (pintype "passive"))
    )
    (net (code "26") (name "/control_9") (class "Default")
      (node (ref "Signal") (pin "9") (pinfunction "9_9") (pintype "passive"))
      (node (ref "U11") (pin "2") (pinfunction "CAT_2") (pintype "passive"))
    )
    (net (code "27") (name "/control_10") (class "Default")
      (node (ref "Signal") (pin "10") (pinfunction "10_10") (pintype "passive"))
    )
    (net (code "28") (name "3.3V") (class "Default")
      (node (ref "AMS1117-3.3") (pin "2") (pinfunction "VOUT_2") (pintype "passive"))
      (node (ref "C18") (pin "2") (pinfunction "2_2") (pintype "passive"))
      (node (ref "C19") (pin "2") (pinfunction "2_2") (pintype "passive"))
      (node (ref "R1") (pin "2") (pinfunction "2_2") (pintype "passive"))
      (node (ref "R10") (pin "2") (pinfunction "2_2") (pintype "passive"))
      (node (ref "R11") (pin "2") (pinfunction "2_2") (pintype "passive"))
      (node (ref "R12") (pin "2") (pinfunction "2_2") (pintype "passive"))
      (node (ref "R19") (pin "2") (pinfunction "2_2") (pintype "passive"))
      (node (ref "R2") (pin "2") (pinfunction "2_2") (pintype "passive"))
      (node (ref "R20") (pin "2") (pinfunction "2_2") (pintype "passive"))
      (node (ref "R21") (pin "2") (pinfunction "2_2") (pintype "passive"))
      (node (ref "R3") (pin "2") (pinfunction "2_2") (pintype "passive"))
    )
    (net (code "29") (name "DGND") (class "Default")
      (node (ref "12V") (pin "10") (pinfunction "10_10") (pintype "passive"))
      (node (ref "12V") (pin "2") (pinfunction "2_2") (pintype "passive"))
      (node (ref "12V") (pin "4") (pinfunction "4_4") (pintype "passive"))
      (node (ref "12V") (pin "6") (pinfunction "6_6") (pintype "passive"))
      (node (ref "12V") (pin "8") (pinfunction "8_8") (pintype "passive"))
      (node (ref "AMS1117-3.3") (pin "1") (pinfunction "ADJ/GND_1") (pintype "passive"))
      (node (ref "C11") (pin "2") (pinfunction "2_2") (pintype "passive"))
      (node (ref "C12") (pin "2") (pinfunction "2_2") (pintype "passive"))
      (node (ref "C14") (pin "2") (pinfunction "2_2") (pintype "passive"))
      (node (ref "C15") (pin "2") (pinfunction "2_2") (pintype "passive"))
      (node (ref "C16") (pin "2") (pinfunction "2_2") (pintype "passive"))
      (node (ref "C17") (pin "2") (pinfunction "2_2") (pintype "passive"))
      (node (ref "C18") (pin "1") (pinfunction "1_1") (pintype "passive"))
      (node (ref "C19") (pin "1") (pinfunction "1_1") (pintype "passive"))
      (node (ref "C21") (pin "1") (pinfunction "1_1") (pintype "passive"))
      (node (ref "C5") (pin "2") (pinfunction "2_2") (pintype "passive"))
      (node (ref "C6") (pin "2") (pinfunction "2_2") (pintype "passive"))
      (node (ref "C8") (pin "2") (pinfunction "2_2") (pintype "passive"))
      (node (ref "C9") (pin "2") (pinfunction "2_2") (pintype "passive"))
      (node (ref "CILIYI") (pin "3") (pinfunction "3_3") (pintype "passive"))
      (node (ref "CILIYI") (pin "6") (pinfunction "6_6") (pintype "passive"))
      (node (ref "CILIYI") (pin "9") (pinfunction "9_9") (pintype "passive"))
      (node (ref "JP1") (pin "2") (pinfunction "2_2") (pintype "passive"))
      (node (ref "JP2") (pin "2") (pinfunction "2_2") (pintype "passive"))
      (node (ref "JP3") (pin "2") (pinfunction "2_2") (pintype "passive"))
      (node (ref "Q1") (pin "2") (pinfunction "E_2") (pintype "passive"))
      (node (ref "Q2") (pin "2") (pinfunction "E_2") (pintype "passive"))
      (node (ref "Q3") (pin "2") (pinfunction "E_2") (pintype "passive"))
      (node (ref "Q4") (pin "2") (pinfunction "E_2") (pintype "passive"))
      (node (ref "Q5") (pin "2") (pinfunction "E_2") (pintype "passive"))
      (node (ref "Q6") (pin "2") (pinfunction "E_2") (pintype "passive"))
      (node (ref "Q7") (pin "2") (pinfunction "E_2") (pintype "passive"))
      (node (ref "Q8") (pin "2") (pinfunction "E_2") (pintype "passive"))
      (node (ref "Q9") (pin "2") (pinfunction "E_2") (pintype "passive"))
      (node (ref "R16") (pin "2") (pinfunction "2_2") (pintype "passive"))
      (node (ref "R17") (pin "2") (pinfunction "2_2") (pintype "passive"))
      (node (ref "R18") (pin "2") (pinfunction "2_2") (pintype "passive"))
      (node (ref "R25") (pin "2") (pinfunction "2_2") (pintype "passive"))
      (node (ref "R26") (pin "2") (pinfunction "2_2") (pintype "passive"))
      (node (ref "R27") (pin "2") (pinfunction "2_2") (pintype "passive"))
      (node (ref "R7") (pin "2") (pinfunction "2_2") (pintype "passive"))
      (node (ref "R8") (pin "2") (pinfunction "2_2") (pintype "passive"))
      (node (ref "R9") (pin "2") (pinfunction "2_2") (pintype "passive"))
      (node (ref "U12") (pin "4") (pinfunction "VO-_4") (pintype "passive"))
      (node (ref "U13") (pin "4") (pinfunction "VO-_4") (pintype "passive"))
      (node (ref "U14") (pin "4") (pinfunction "VO-_4") (pintype "passive"))
      (node (ref "U15") (pin "4") (pinfunction "VO-_4") (pintype "passive"))
      (node (ref "U16") (pin "3") (pinfunction "GROUND_3") (pintype "passive"))
      (node (ref "Z2") (pin "1") (pinfunction "A_1") (pintype "passive"))
      (node (ref "Z3") (pin "1") (pinfunction "A_1") (pintype "passive"))
      (node (ref "Z4") (pin "1") (pinfunction "A_1") (pintype "passive"))
      (node (ref "Z5") (pin "1") (pinfunction "A_1") (pintype "passive"))
    )
    (net (code "30") (name "Net-(D1-A)") (class "Default")
      (node (ref "D1") (pin "1") (pinfunction "A_1") (pintype "passive"))
      (node (ref "Q1") (pin "3") (pinfunction "C_3") (pintype "passive"))
      (node (ref "RLY1") (pin "2") (pinfunction "COIL_2") (pintype "passive"))
    )
    (net (code "31") (name "Net-(D2-A)") (class "Default")
      (node (ref "D2") (pin "1") (pinfunction "A_1") (pintype "passive"))
      (node (ref "Q2") (pin "3") (pinfunction "C_3") (pintype "passive"))
      (node (ref "RLY2") (pin "2") (pinfunction "COIL_2") (pintype "passive"))
    )
    (net (code "32") (name "Net-(D3-A)") (class "Default")
      (node (ref "D3") (pin "1") (pinfunction "A_1") (pintype "passive"))
      (node (ref "Q3") (pin "3") (pinfunction "C_3") (pintype "passive"))
      (node (ref "RLY3") (pin "2") (pinfunction "COIL_2") (pintype "passive"))
    )
    (net (code "33") (name "Net-(D4-A)") (class "Default")
      (node (ref "D4") (pin "1") (pinfunction "A_1") (pintype "passive"))
      (node (ref "Q4") (pin "3") (pinfunction "C_3") (pintype "passive"))
      (node (ref "RLY4") (pin "2") (pinfunction "COIL_2") (pintype "passive"))
    )
    (net (code "34") (name "Net-(D5-A)") (class "Default")
      (node (ref "D5") (pin "1") (pinfunction "A_1") (pintype "passive"))
      (node (ref "Q5") (pin "3") (pinfunction "C_3") (pintype "passive"))
      (node (ref "RLY5") (pin "2") (pinfunction "COIL_2") (pintype "passive"))
    )
    (net (code "35") (name "Net-(D6-A)") (class "Default")
      (node (ref "D6") (pin "1") (pinfunction "A_1") (pintype "passive"))
      (node (ref "Q6") (pin "3") (pinfunction "C_3") (pintype "passive"))
      (node (ref "RLY6") (pin "2") (pinfunction "COIL_2") (pintype "passive"))
    )
    (net (code "36") (name "Net-(D7-A)") (class "Default")
      (node (ref "D7") (pin "1") (pinfunction "A_1") (pintype "passive"))
      (node (ref "Q7") (pin "3") (pinfunction "C_3") (pintype "passive"))
      (node (ref "RLY7") (pin "2") (pinfunction "COIL_2") (pintype "passive"))
    )
    (net (code "37") (name "Net-(D8-A)") (class "Default")
      (node (ref "D8") (pin "1") (pinfunction "A_1") (pintype "passive"))
      (node (ref "Q8") (pin "3") (pinfunction "C_3") (pintype "passive"))
      (node (ref "RLY8") (pin "2") (pinfunction "COIL_2") (pintype "passive"))
    )
    (net (code "38") (name "Net-(D9-A)") (class "Default")
      (node (ref "D9") (pin "1") (pinfunction "A_1") (pintype "passive"))
      (node (ref "Q9") (pin "3") (pinfunction "C_3") (pintype "passive"))
      (node (ref "RLY9") (pin "2") (pinfunction "COIL_2") (pintype "passive"))
    )
    (net (code "39") (name "Net-(Q1-B)") (class "Default")
      (node (ref "Q1") (pin "1") (pinfunction "B_1") (pintype "passive"))
      (node (ref "R4") (pin "2") (pinfunction "2_2") (pintype "passive"))
    )
    (net (code "40") (name "Net-(Q2-B)") (class "Default")
      (node (ref "Q2") (pin "1") (pinfunction "B_1") (pintype "passive"))
      (node (ref "R5") (pin "2") (pinfunction "2_2") (pintype "passive"))
    )
    (net (code "41") (name "Net-(Q3-B)") (class "Default")
      (node (ref "Q3") (pin "1") (pinfunction "B_1") (pintype "passive"))
      (node (ref "R6") (pin "2") (pinfunction "2_2") (pintype "passive"))
    )
    (net (code "42") (name "Net-(Q4-B)") (class "Default")
      (node (ref "Q4") (pin "1") (pinfunction "B_1") (pintype "passive"))
      (node (ref "R13") (pin "2") (pinfunction "2_2") (pintype "passive"))
    )
    (net (code "43") (name "Net-(Q5-B)") (class "Default")
      (node (ref "Q5") (pin "1") (pinfunction "B_1") (pintype "passive"))
      (node (ref "R14") (pin "2") (pinfunction "2_2") (pintype "passive"))
    )
    (net (code "44") (name "Net-(Q6-B)") (class "Default")
      (node (ref "Q6") (pin "1") (pinfunction "B_1") (pintype "passive"))
      (node (ref "R15") (pin "2") (pinfunction "2_2") (pintype "passive"))
    )
    (net (code "45") (name "Net-(Q7-B)") (class "Default")
      (node (ref "Q7") (pin "1") (pinfunction "B_1") (pintype "passive"))
      (node (ref "R22") (pin "2") (pinfunction "2_2") (pintype "passive"))
    )
    (net (code "46") (name "Net-(Q8-B)") (class "Default")
      (node (ref "Q8") (pin "1") (pinfunction "B_1") (pintype "passive"))
      (node (ref "R23") (pin "2") (pinfunction "2_2") (pintype "passive"))
    )
    (net (code "47") (name "Net-(Q9-B)") (class "Default")
      (node (ref "Q9") (pin "1") (pinfunction "B_1") (pintype "passive"))
      (node (ref "R24") (pin "2") (pinfunction "2_2") (pintype "passive"))
    )
    (net (code "48") (name "Net-(U1-AN)") (class "Default")
      (node (ref "R1") (pin "1") (pinfunction "1_1") (pintype "passive"))
      (node (ref "U1") (pin "1") (pinfunction "AN_1") (pintype "passive"))
    )
    (net (code "49") (name "Net-(U1-EM)") (class "Default")
      (node (ref "R4") (pin "1") (pinfunction "1_1") (pintype "passive"))
      (node (ref "R7") (pin "1") (pinfunction "1_1") (pintype "passive"))
      (node (ref "U1") (pin "3") (pinfunction "EM_3") (pintype "passive"))
    )
    (net (code "50") (name "Net-(U2-AN)") (class "Default")
      (node (ref "R2") (pin "1") (pinfunction "1_1") (pintype "passive"))
      (node (ref "U2") (pin "1") (pinfunction "AN_1") (pintype "passive"))
    )
    (net (code "51") (name "Net-(U2-EM)") (class "Default")
      (node (ref "R5") (pin "1") (pinfunction "1_1") (pintype "passive"))
      (node (ref "R8") (pin "1") (pinfunction "1_1") (pintype "passive"))
      (node (ref "U2") (pin "3") (pinfunction "EM_3") (pintype "passive"))
    )
    (net (code "52") (name "Net-(U3-AN)") (class "Default")
      (node (ref "R3") (pin "1") (pinfunction "1_1") (pintype "passive"))
      (node (ref "U3") (pin "1") (pinfunction "AN_1") (pintype "passive"))
    )
    (net (code "53") (name "Net-(U3-EM)") (class "Default")
      (node (ref "R6") (pin "1") (pinfunction "1_1") (pintype "passive"))
      (node (ref "R9") (pin "1") (pinfunction "1_1") (pintype "passive"))
      (node (ref "U3") (pin "3") (pinfunction "EM_3") (pintype "passive"))
    )
    (net (code "54") (name "Net-(U4-AN)") (class "Default")
      (node (ref "R10") (pin "1") (pinfunction "1_1") (pintype "passive"))
      (node (ref "U4") (pin "1") (pinfunction "AN_1") (pintype "passive"))
    )
    (net (code "55") (name "Net-(U4-EM)") (class "Default")
      (node (ref "R13") (pin "1") (pinfunction "1_1") (pintype "passive"))
      (node (ref "R16") (pin "1") (pinfunction "1_1") (pintype "passive"))
      (node (ref "U4") (pin "3") (pinfunction "EM_3") (pintype "passive"))
    )
    (net (code "56") (name "Net-(U5-AN)") (class "Default")
      (node (ref "R11") (pin "1") (pinfunction "1_1") (pintype "passive"))
      (node (ref "U5") (pin "1") (pinfunction "AN_1") (pintype "passive"))
    )
    (net (code "57") (name "Net-(U5-EM)") (class "Default")
      (node (ref "R14") (pin "1") (pinfunction "1_1") (pintype "passive"))
      (node (ref "R17") (pin "1") (pinfunction "1_1") (pintype "passive"))
      (node (ref "U5") (pin "3") (pinfunction "EM_3") (pintype "passive"))
    )
    (net (code "58") (name "Net-(U6-AN)") (class "Default")
      (node (ref "R12") (pin "1") (pinfunction "1_1") (pintype "passive"))
      (node (ref "U6") (pin "1") (pinfunction "AN_1") (pintype "passive"))
    )
    (net (code "59") (name "Net-(U6-EM)") (class "Default")
      (node (ref "R15") (pin "1") (pinfunction "1_1") (pintype "passive"))
      (node (ref "R18") (pin "1") (pinfunction "1_1") (pintype "passive"))
      (node (ref "U6") (pin "3") (pinfunction "EM_3") (pintype "passive"))
    )
    (net (code "60") (name "Net-(U7-+VIN)") (class "Default")
      (node (ref "C1") (pin "1") (pinfunction "1_1") (pintype "passive"))
      (node (ref "R31") (pin "2") (pinfunction "2_2") (pintype "passive"))
      (node (ref "U7") (pin "2") (pinfunction "+VIN_2") (pintype "passive"))
    )
    (net (code "61") (name "Net-(U9-AN)") (class "Default")
      (node (ref "R19") (pin "1") (pinfunction "1_1") (pintype "passive"))
      (node (ref "U9") (pin "1") (pinfunction "AN_1") (pintype "passive"))
    )
    (net (code "62") (name "Net-(U9-EM)") (class "Default")
      (node (ref "R22") (pin "1") (pinfunction "1_1") (pintype "passive"))
      (node (ref "R25") (pin "1") (pinfunction "1_1") (pintype "passive"))
      (node (ref "U9") (pin "3") (pinfunction "EM_3") (pintype "passive"))
    )
    (net (code "63") (name "Net-(U10-AN)") (class "Default")
      (node (ref "R20") (pin "1") (pinfunction "1_1") (pintype "passive"))
      (node (ref "U10") (pin "1") (pinfunction "AN_1") (pintype "passive"))
    )
    (net (code "64") (name "Net-(U10-EM)") (class "Default")
      (node (ref "R23") (pin "1") (pinfunction "1_1") (pintype "passive"))
      (node (ref "R26") (pin "1") (pinfunction "1_1") (pintype "passive"))
      (node (ref "U10") (pin "3") (pinfunction "EM_3") (pintype "passive"))
    )
    (net (code "65") (name "Net-(U11-AN)") (class "Default")
      (node (ref "R21") (pin "1") (pinfunction "1_1") (pintype "passive"))
      (node (ref "U11") (pin "1") (pinfunction "AN_1") (pintype "passive"))
    )
    (net (code "66") (name "Net-(U11-EM)") (class "Default")
      (node (ref "R24") (pin "1") (pinfunction "1_1") (pintype "passive"))
      (node (ref "R27") (pin "1") (pinfunction "1_1") (pintype "passive"))
      (node (ref "U11") (pin "3") (pinfunction "EM_3") (pintype "passive"))
    )
    (net (code "67") (name "Net-(U12-VIN+)") (class "Default")
      (node (ref "C4") (pin "1") (pinfunction "1_1") (pintype "passive"))
      (node (ref "R32") (pin "2") (pinfunction "2_2") (pintype "passive"))
      (node (ref "U12") (pin "1") (pinfunction "VIN+_1") (pintype "passive"))
    )
    (net (code "68") (name "Net-(U13-VIN+)") (class "Default")
      (node (ref "C7") (pin "1") (pinfunction "1_1") (pintype "passive"))
      (node (ref "R33") (pin "2") (pinfunction "2_2") (pintype "passive"))
      (node (ref "U13") (pin "1") (pinfunction "VIN+_1") (pintype "passive"))
    )
    (net (code "69") (name "Net-(U14-VIN+)") (class "Default")
      (node (ref "C10") (pin "1") (pinfunction "1_1") (pintype "passive"))
      (node (ref "R34") (pin "2") (pinfunction "2_2") (pintype "passive"))
      (node (ref "U14") (pin "1") (pinfunction "VIN+_1") (pintype "passive"))
    )
    (net (code "70") (name "Net-(U15-VIN+)") (class "Default")
      (node (ref "C13") (pin "1") (pinfunction "1_1") (pintype "passive"))
      (node (ref "R35") (pin "2") (pinfunction "2_2") (pintype "passive"))
      (node (ref "U15") (pin "1") (pinfunction "VIN+_1") (pintype "passive"))
    )
    (net (code "71") (name "Net-(U16-CAP+)") (class "Default")
      (node (ref "C20") (pin "1") (pinfunction "1_1") (pintype "passive"))
      (node (ref "U16") (pin "2") (pinfunction "CAP+_2") (pintype "passive"))
    )
    (net (code "72") (name "Net-(U16-CAP-)") (class "Default")
      (node (ref "C20") (pin "2") (pinfunction "2_2") (pintype "passive"))
      (node (ref "U16") (pin "4") (pinfunction "CAP-_4") (pintype "passive"))
    )
    (net (code "73") (name "V-5V") (class "Default")
      (node (ref "AMS1117-3.3") (pin "3") (pinfunction "VIN_3") (pintype "passive"))
      (node (ref "C16") (pin "1") (pinfunction "1_1") (pintype "passive"))
      (node (ref "C17") (pin "1") (pinfunction "1_1") (pintype "passive"))
      (node (ref "C5") (pin "1") (pinfunction "1_1") (pintype "passive"))
      (node (ref "C6") (pin "1") (pinfunction "1_1") (pintype "passive"))
      (node (ref "C8") (pin "1") (pinfunction "1_1") (pintype "passive"))
      (node (ref "C9") (pin "1") (pinfunction "1_1") (pintype "passive"))
      (node (ref "D1") (pin "2") (pinfunction "K_2") (pintype "passive"))
      (node (ref "D2") (pin "2") (pinfunction "K_2") (pintype "passive"))
      (node (ref "D3") (pin "2") (pinfunction "K_2") (pintype "passive"))
      (node (ref "D4") (pin "2") (pinfunction "K_2") (pintype "passive"))
      (node (ref "D5") (pin "2") (pinfunction "K_2") (pintype "passive"))
      (node (ref "D6") (pin "2") (pinfunction "K_2") (pintype "passive"))
      (node (ref "D7") (pin "2") (pinfunction "K_2") (pintype "passive"))
      (node (ref "D8") (pin "2") (pinfunction "K_2") (pintype "passive"))
      (node (ref "D9") (pin "2") (pinfunction "K_2") (pintype "passive"))
      (node (ref "JP1") (pin "1") (pinfunction "1_1") (pintype "passive"))
      (node (ref "JP2") (pin "1") (pinfunction "1_1") (pintype "passive"))
      (node (ref "JP3") (pin "1") (pinfunction "1_1") (pintype "passive"))
      (node (ref "RLY1") (pin "1") (pinfunction "COIL_1") (pintype "passive"))
      (node (ref "RLY2") (pin "1") (pinfunction "COIL_1") (pintype "passive"))
      (node (ref "RLY3") (pin "1") (pinfunction "COIL_1") (pintype "passive"))
      (node (ref "RLY4") (pin "1") (pinfunction "COIL_1") (pintype "passive"))
      (node (ref "RLY5") (pin "1") (pinfunction "COIL_1") (pintype "passive"))
      (node (ref "RLY6") (pin "1") (pinfunction "COIL_1") (pintype "passive"))
      (node (ref "RLY7") (pin "1") (pinfunction "COIL_1") (pintype "passive"))
      (node (ref "RLY8") (pin "1") (pinfunction "COIL_1") (pintype "passive"))
      (node (ref "RLY9") (pin "1") (pinfunction "COIL_1") (pintype "passive"))
      (node (ref "U1") (pin "4") (pinfunction "COL_4") (pintype "passive"))
      (node (ref "U10") (pin "4") (pinfunction "COL_4") (pintype "passive"))
      (node (ref "U11") (pin "4") (pinfunction "COL_4") (pintype "passive"))
      (node (ref "U12") (pin "6") (pinfunction "VO+_6") (pintype "passive"))
      (node (ref "U13") (pin "6") (pinfunction "VO+_6") (pintype "passive"))
      (node (ref "U2") (pin "4") (pinfunction "COL_4") (pintype "passive"))
      (node (ref "U3") (pin "4") (pinfunction "COL_4") (pintype "passive"))
      (node (ref "U4") (pin "4") (pinfunction "COL_4") (pintype "passive"))
      (node (ref "U5") (pin "4") (pinfunction "COL_4") (pintype "passive"))
      (node (ref "U6") (pin "4") (pinfunction "COL_4") (pintype "passive"))
      (node (ref "U9") (pin "4") (pinfunction "COL_4") (pintype "passive"))
      (node (ref "Z2") (pin "2") (pinfunction "K_2") (pintype "passive"))
      (node (ref "Z3") (pin "2") (pinfunction "K_2") (pintype "passive"))
    )
    (net (code "74") (name "unconnected-(RLY1-NC-Pad3)") (class "Default")
      (node (ref "RLY1") (pin "3") (pinfunction "NC_3") (pintype "passive"))
    )
    (net (code "75") (name "unconnected-(RLY2-NC-Pad3)") (class "Default")
      (node (ref "RLY2") (pin "3") (pinfunction "NC_3") (pintype "passive"))
    )
    (net (code "76") (name "unconnected-(RLY3-NC-Pad3)") (class "Default")
      (node (ref "RLY3") (pin "3") (pinfunction "NC_3") (pintype "passive"))
    )
    (net (code "77") (name "unconnected-(RLY4-NC-Pad3)") (class "Default")
      (node (ref "RLY4") (pin "3") (pinfunction "NC_3") (pintype "passive"))
    )
    (net (code "78") (name "unconnected-(RLY5-NC-Pad3)") (class "Default")
      (node (ref "RLY5") (pin "3") (pinfunction "NC_3") (pintype "passive"))
    )
    (net (code "79") (name "unconnected-(RLY6-NC-Pad3)") (class "Default")
      (node (ref "RLY6") (pin "3") (pinfunction "NC_3") (pintype "passive"))
    )
    (net (code "80") (name "unconnected-(RLY7-NC-Pad3)") (class "Default")
      (node (ref "RLY7") (pin "3") (pinfunction "NC_3") (pintype "passive"))
    )
    (net (code "81") (name "unconnected-(RLY8-NC-Pad3)") (class "Default")
      (node (ref "RLY8") (pin "3") (pinfunction "NC_3") (pintype "passive"))
    )
    (net (code "82") (name "unconnected-(RLY9-NC-Pad3)") (class "Default")
      (node (ref "RLY9") (pin "3") (pinfunction "NC_3") (pintype "passive"))
    )
    (net (code "83") (name "unconnected-(U7-CTRL-Pad6)") (class "Default")
      (node (ref "U7") (pin "6") (pinfunction "CTRL_6") (pintype "passive"))
    )
    (net (code "84") (name "unconnected-(U7-Trim-Pad4)") (class "Default")
      (node (ref "U7") (pin "4") (pinfunction "Trim_4") (pintype "passive"))
    )
    (net (code "85") (name "unconnected-(U12-CNT-Pad3)") (class "Default")
      (node (ref "U12") (pin "3") (pinfunction "CNT_3") (pintype "passive"))
    )
    (net (code "86") (name "unconnected-(U13-CNT-Pad3)") (class "Default")
      (node (ref "U13") (pin "3") (pinfunction "CNT_3") (pintype "passive"))
    )
    (net (code "87") (name "unconnected-(U14-CNT-Pad3)") (class "Default")
      (node (ref "U14") (pin "3") (pinfunction "CNT_3") (pintype "passive"))
    )
    (net (code "88") (name "unconnected-(U15-CNT-Pad3)") (class "Default")
      (node (ref "U15") (pin "3") (pinfunction "CNT_3") (pintype "passive"))
    )
    (net (code "89") (name "unconnected-(U16-LV-Pad6)") (class "Default")
      (node (ref "U16") (pin "6") (pinfunction "LV_6") (pintype "passive"))
    )
    (net (code "90") (name "unconnected-(U16-OSC-Pad7)") (class "Default")
      (node (ref "U16") (pin "7") (pinfunction "OSC_7") (pintype "passive"))
    )
    (net (code "91") (name "unconnected-(U16-TEST-Pad1)") (class "Default")
      (node (ref "U16") (pin "1") (pinfunction "TEST_1") (pintype "passive"))
    )
  )
)
